# rgb-led-cc-driver-mk-3_0.net
KiCad netlist of a schematic drawn in EAGLE
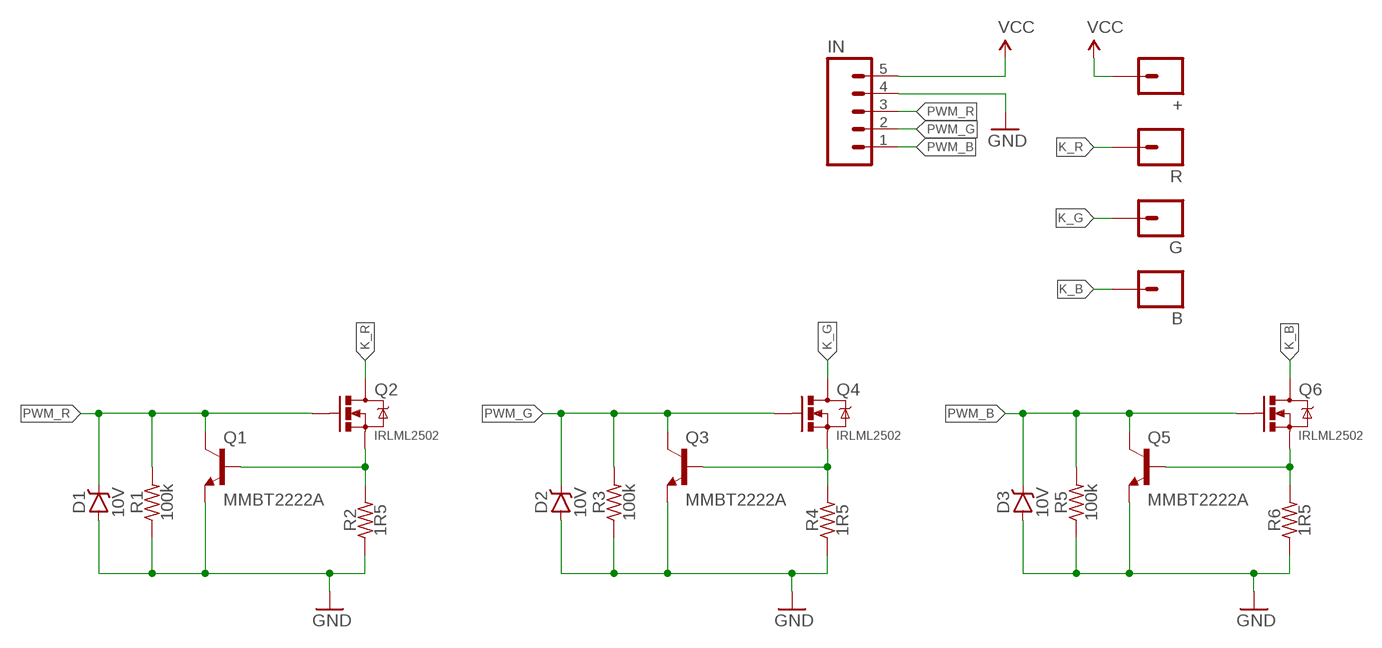
[diagram p0: schematic, sheet 1]

(export (version "E")
  (design (tool "Eeschema 10.0.6"))
  (components
    (comp (ref "+")
      (value "M01PTH_2MM")
      (footprint "eagle-import:1X01_2MM")
      (libsource (lib "eagle-import") (part "M01PTH_2MM"))
    )
    (comp (ref "B")
      (value "M01PTH_2MM")
      (footprint "eagle-import:1X01_2MM")
      (libsource (lib "eagle-import") (part "M01PTH_2MM"))
    )
    (comp (ref "D1")
      (value "10V")
      (footprint "eagle-import:SOD123-ZENER")
      (libsource (lib "eagle-import") (part "DIODE-ZENERSOD123"))
    )
    (comp (ref "D2")
      (value "10V")
      (footprint "eagle-import:SOD123-ZENER")
      (libsource (lib "eagle-import") (part "DIODE-ZENERSOD123"))
    )
    (comp (ref "D3")
      (value "10V")
      (footprint "eagle-import:SOD123-ZENER")
      (libsource (lib "eagle-import") (part "DIODE-ZENERSOD123"))
    )
    (comp (ref "G")
      (value "M01PTH_2MM")
      (footprint "eagle-import:1X01_2MM")
      (libsource (lib "eagle-import") (part "M01PTH_2MM"))
    )
    (comp (ref "IN")
      (value "M05PTH")
      (footprint "eagle-import:1X05")
      (libsource (lib "eagle-import") (part "M05PTH"))
    )
    (comp (ref "Q1")
      (value "MMBT2222A")
      (footprint "eagle-import:SOT23")
      (libsource (lib "eagle-import") (part "TRANSISTOR_NPNMMBT2222A"))
    )
    (comp (ref "Q2")
      (value "IRLML2502")
      (footprint "eagle-import:SOT23")
      (libsource (lib "eagle-import") (part "MOSFET-NCHANNELIRLML2502"))
    )
    (comp (ref "Q3")
      (value "MMBT2222A")
      (footprint "eagle-import:SOT23")
      (libsource (lib "eagle-import") (part "TRANSISTOR_NPNMMBT2222A"))
    )
    (comp (ref "Q4")
      (value "IRLML2502")
      (footprint "eagle-import:SOT23")
      (libsource (lib "eagle-import") (part "MOSFET-NCHANNELIRLML2502"))
    )
    (comp (ref "Q5")
      (value "MMBT2222A")
      (footprint "eagle-import:SOT23")
      (libsource (lib "eagle-import") (part "TRANSISTOR_NPNMMBT2222A"))
    )
    (comp (ref "Q6")
      (value "IRLML2502")
      (footprint "eagle-import:SOT23")
      (libsource (lib "eagle-import") (part "MOSFET-NCHANNELIRLML2502"))
    )
    (comp (ref "R")
      (value "M01PTH_2MM")
      (footprint "eagle-import:1X01_2MM")
      (libsource (lib "eagle-import") (part "M01PTH_2MM"))
    )
    (comp (ref "R1")
      (value "100k")
      (footprint "eagle-import:R0805")
      (libsource (lib "eagle-import") (part "RESISTORR0805"))
    )
    (comp (ref "R2")
      (value "1R5")
      (footprint "eagle-import:R1206")
      (libsource (lib "eagle-import") (part "RESISTORR1206"))
    )
    (comp (ref "R3")
      (value "100k")
      (footprint "eagle-import:R0805")
      (libsource (lib "eagle-import") (part "RESISTORR0805"))
    )
    (comp (ref "R4")
      (value "1R5")
      (footprint "eagle-import:R1206")
      (libsource (lib "eagle-import") (part "RESISTORR1206"))
    )
    (comp (ref "R5")
      (value "100k")
      (footprint "eagle-import:R0805")
      (libsource (lib "eagle-import") (part "RESISTORR0805"))
    )
    (comp (ref "R6")
      (value "1R5")
      (footprint "eagle-import:R1206")
      (libsource (lib "eagle-import") (part "RESISTORR1206"))
    )
  )
  (nets
    (net (code "1") (name "GND") (class "Default")
      (node (ref "D1") (pin "A") (pinfunction "A_A") (pintype "passive"))
      (node (ref "D2") (pin "A") (pinfunction "A_A") (pintype "passive"))
      (node (ref "D3") (pin "A") (pinfunction "A_A") (pintype "passive"))
      (node (ref "IN") (pin "4") (pinfunction "4_4") (pintype "passive"))
      (node (ref "Q1") (pin "2") (pinfunction "E_2") (pintype "passive"))
      (node (ref "Q3") (pin "2") (pinfunction "E_2") (pintype "passive"))
      (node (ref "Q5") (pin "2") (pinfunction "E_2") (pintype "passive"))
      (node (ref "R1") (pin "1") (pinfunction "1_1") (pintype "passive"))
      (node (ref "R2") (pin "1") (pinfunction "1_1") (pintype "passive"))
      (node (ref "R3") (pin "1") (pinfunction "1_1") (pintype "passive"))
      (node (ref "R4") (pin "1") (pinfunction "1_1") (pintype "passive"))
      (node (ref "R5") (pin "1") (pinfunction "1_1") (pintype "passive"))
      (node (ref "R6") (pin "1") (pinfunction "1_1") (pintype "passive"))
    )
    (net (code "2") (name "K_B") (class "Default")
      (node (ref "B") (pin "1") (pinfunction "1_1") (pintype "passive"))
      (node (ref "Q6") (pin "3") (pinfunction "D_3") (pintype "passive"))
    )
    (net (code "3") (name "K_G") (class "Default")
      (node (ref "G") (pin "1") (pinfunction "1_1") (pintype "passive"))
      (node (ref "Q4") (pin "3") (pinfunction "D_3") (pintype "passive"))
    )
    (net (code "4") (name "K_R") (class "Default")
      (node (ref "Q2") (pin "3") (pinfunction "D_3") (pintype "passive"))
      (node (ref "R") (pin "1") (pinfunction "1_1") (pintype "passive"))
    )
    (net (code "5") (name "Net-(Q1-B)") (class "Default")
      (node (ref "Q1") (pin "1") (pinfunction "B_1") (pintype "passive"))
      (node (ref "Q2") (pin "2") (pinfunction "S_2") (pintype "passive"))
      (node (ref "R2") (pin "2") (pinfunction "2_2") (pintype "passive"))
    )
    (net (code "6") (name "Net-(Q3-B)") (class "Default")
      (node (ref "Q3") (pin "1") (pinfunction "B_1") (pintype "passive"))
      (node (ref "Q4") (pin "2") (pinfunction "S_2") (pintype "passive"))
      (node (ref "R4") (pin "2") (pinfunction "2_2") (pintype "passive"))
    )
    (net (code "7") (name "Net-(Q5-B)") (class "Default")
      (node (ref "Q5") (pin "1") (pinfunction "B_1") (pintype "passive"))
      (node (ref "Q6") (pin "2") (pinfunction "S_2") (pintype "passive"))
      (node (ref "R6") (pin "2") (pinfunction "2_2") (pintype "passive"))
    )
    (net (code "8") (name "PWM_B") (class "Default")
      (node (ref "D3") (pin "C") (pinfunction "C_C") (pintype "passive"))
      (node (ref "IN") (pin "1") (pinfunction "1_1") (pintype "passive"))
      (node (ref "Q5") (pin "3") (pinfunction "C_3") (pintype "passive"))
      (node (ref "Q6") (pin "1") (pinfunction "G_1") (pintype "passive"))
      (node (ref "R5") (pin "2") (pinfunction "2_2") (pintype "passive"))
    )
    (net (code "9") (name "PWM_G") (class "Default")
      (node (ref "D2") (pin "C") (pinfunction "C_C") (pintype "passive"))
      (node (ref "IN") (pin "2") (pinfunction "2_2") (pintype "passive"))
      (node (ref "Q3") (pin "3") (pinfunction "C_3") (pintype "passive"))
      (node (ref "Q4") (pin "1") (pinfunction "G_1") (pintype "passive"))
      (node (ref "R3") (pin "2") (pinfunction "2_2") (pintype "passive"))
    )
    (net (code "10") (name "PWM_R") (class "Default")
      (node (ref "D1") (pin "C") (pinfunction "C_C") (pintype "passive"))
      (node (ref "IN") (pin "3") (pinfunction "3_3") (pintype "passive"))
      (node (ref "Q1") (pin "3") (pinfunction "C_3") (pintype "passive"))
      (node (ref "Q2") (pin "1") (pinfunction "G_1") (pintype "passive"))
      (node (ref "R1") (pin "2") (pinfunction "2_2") (pintype "passive"))
    )
    (net (code "11") (name "VCC") (class "Default")
      (node (ref "+") (pin "1") (pinfunction "1_1") (pintype "passive"))
      (node (ref "IN") (pin "5") (pinfunction "5_5") (pintype "passive"))
    )
  )
)
